# kaimat.net
KiCad netlist of a schematic drawn in EAGLE
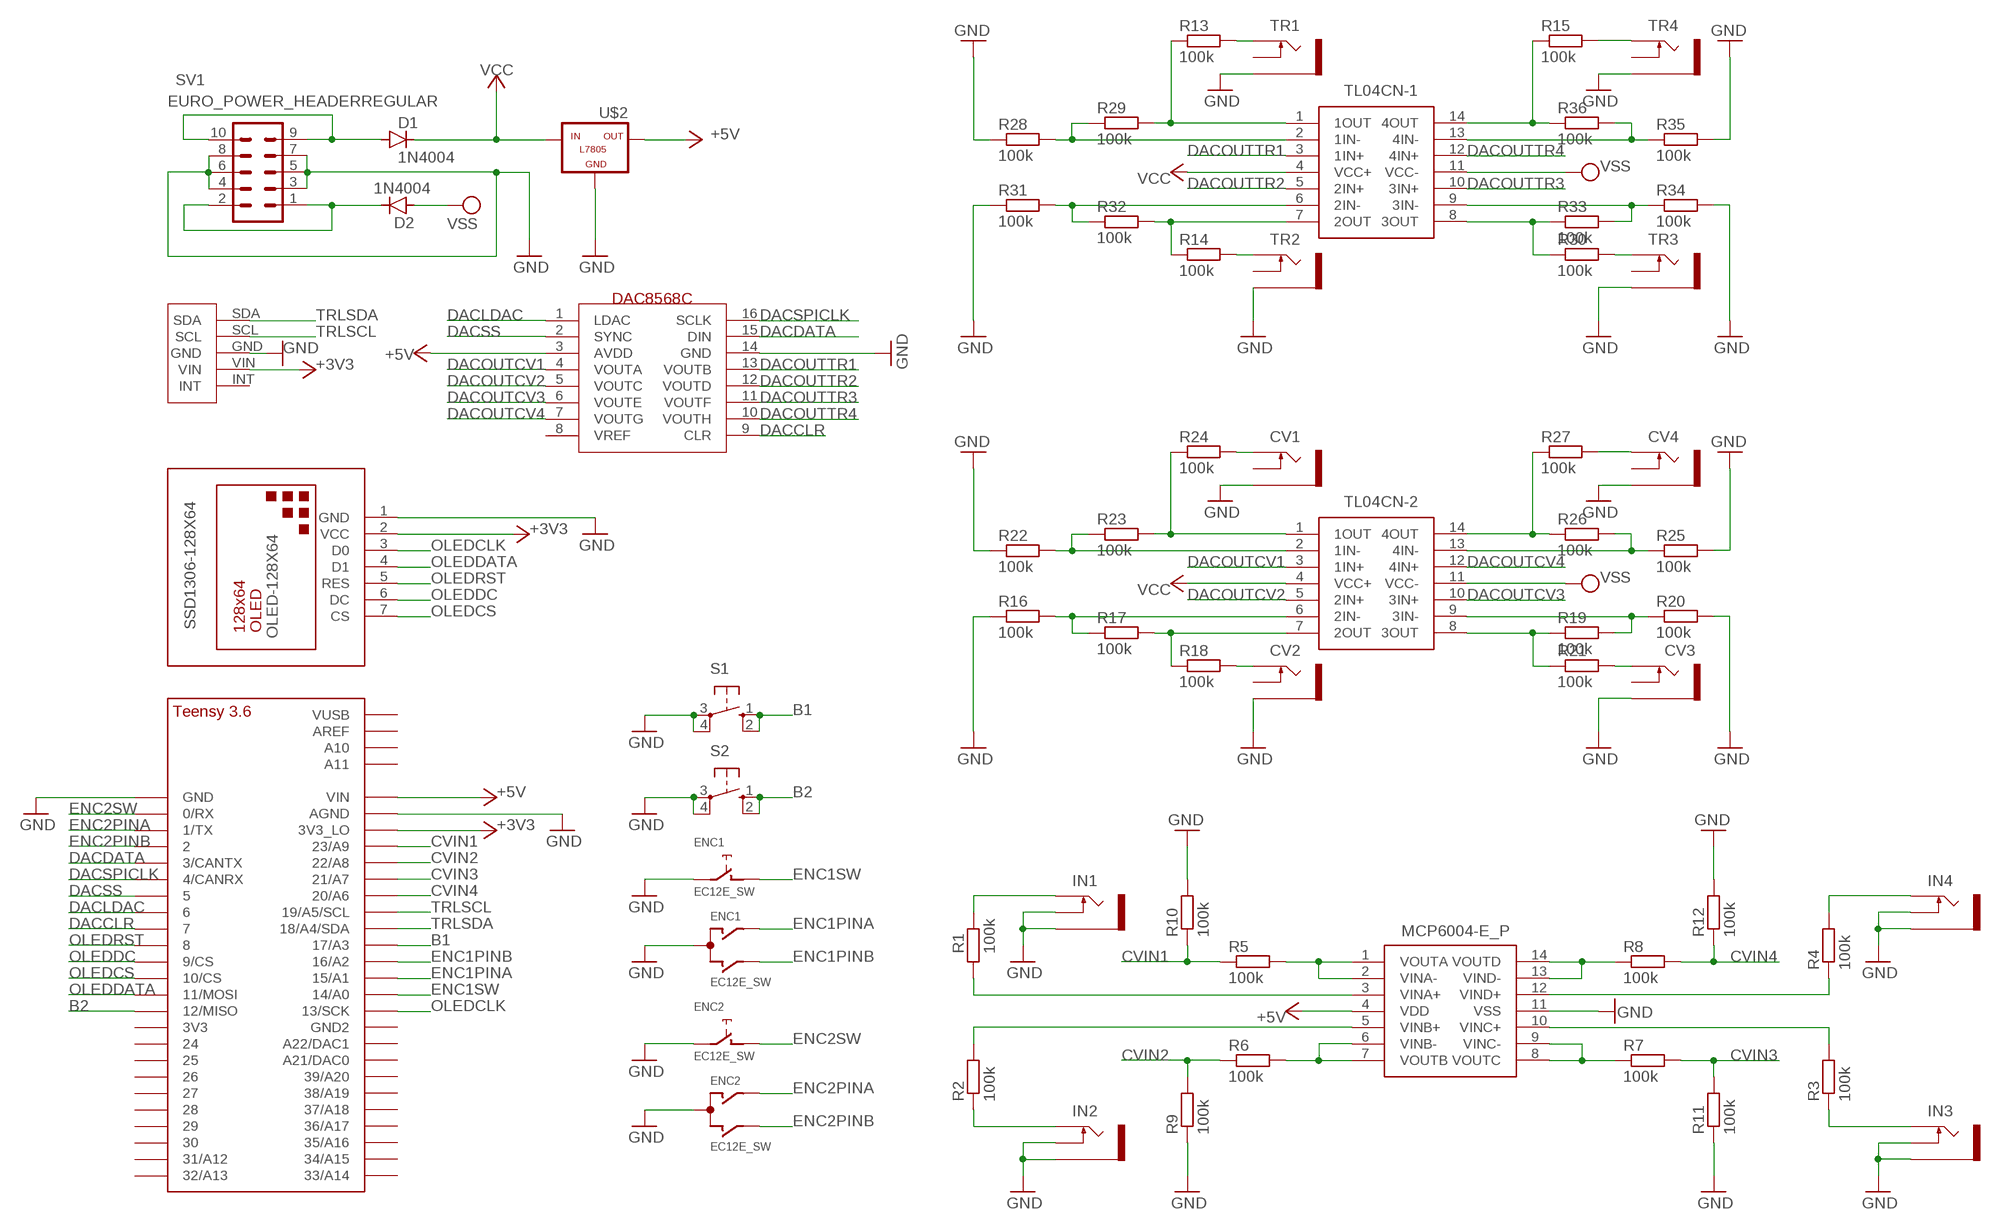
[diagram p0: schematic, sheet 1]

(export (version "E")
  (design (tool "Eeschema 10.0.6"))
  (components
    (comp (ref "CV1")
      (value "THONKICONNNEW")
      (footprint "eagle-import:WQP-PJ301M-12_JACK")
      (libsource (lib "eagle-import") (part "THONKICONNNEW"))
    )
    (comp (ref "CV2")
      (value "THONKICONNNEW")
      (footprint "eagle-import:WQP-PJ301M-12_JACK")
      (libsource (lib "eagle-import") (part "THONKICONNNEW"))
    )
    (comp (ref "CV3")
      (value "THONKICONNNEW")
      (footprint "eagle-import:WQP-PJ301M-12_JACK")
      (libsource (lib "eagle-import") (part "THONKICONNNEW"))
    )
    (comp (ref "CV4")
      (value "THONKICONNNEW")
      (footprint "eagle-import:WQP-PJ301M-12_JACK")
      (libsource (lib "eagle-import") (part "THONKICONNNEW"))
    )
    (comp (ref "D1")
      (value "1N4004")
      (footprint "eagle-import:DO41-10")
      (libsource (lib "eagle-import") (part "1N4004"))
    )
    (comp (ref "D2")
      (value "1N4004")
      (footprint "eagle-import:DO41-10")
      (libsource (lib "eagle-import") (part "1N4004"))
    )
    (comp (ref "DAC8568C")
      (value "DAC8568C")
      (footprint "eagle-import:TSSOP16")
      (libsource (lib "eagle-import") (part "DAC8568C"))
    )
    (comp (ref "ENC1")
      (value "EC12E_SW")
      (footprint "eagle-import:ALPS_EC12E_SW")
      (fields (field (name "MPN") "EC12E2424407"))
      (libsource (lib "eagle-import") (part "EC12E_SW"))
    )
    (comp (ref "ENC2")
      (value "EC12E_SW")
      (footprint "eagle-import:ALPS_EC12E_SW")
      (fields (field (name "MPN") "EC12E2424407"))
      (libsource (lib "eagle-import") (part "EC12E_SW"))
    )
    (comp (ref "IN1")
      (value "THONKICONNNEW")
      (footprint "eagle-import:WQP-PJ301M-12_JACK")
      (libsource (lib "eagle-import") (part "THONKICONNNEW"))
    )
    (comp (ref "IN2")
      (value "THONKICONNNEW")
      (footprint "eagle-import:WQP-PJ301M-12_JACK")
      (libsource (lib "eagle-import") (part "THONKICONNNEW"))
    )
    (comp (ref "IN3")
      (value "THONKICONNNEW")
      (footprint "eagle-import:WQP-PJ301M-12_JACK")
      (libsource (lib "eagle-import") (part "THONKICONNNEW"))
    )
    (comp (ref "IN4")
      (value "THONKICONNNEW")
      (footprint "eagle-import:WQP-PJ301M-12_JACK")
      (libsource (lib "eagle-import") (part "THONKICONNNEW"))
    )
    (comp (ref "MCP6004-E_P")
      (value "MCP6004-E_P")
      (footprint "eagle-import:DIP781W56P254L1918H533Q14N")
      (fields
        (field (name "MANUFACTURER_PART_NUMBER") "mcp6004-e/p")
        (field (name "MOUSER_PART_NUMBER") "579-MCP6004-E/P")
        (field (name "RS_PART_NUMBER") "7386178P")
      )
      (libsource (lib "eagle-import") (part "MCP6004-E_P"))
    )
    (comp (ref "R1")
      (value "100k")
      (footprint "eagle-import:R0805")
      (libsource (lib "eagle-import") (part "R-EU_R0805"))
    )
    (comp (ref "R2")
      (value "100k")
      (footprint "eagle-import:R0805")
      (libsource (lib "eagle-import") (part "R-EU_R0805"))
    )
    (comp (ref "R3")
      (value "100k")
      (footprint "eagle-import:R0805")
      (libsource (lib "eagle-import") (part "R-EU_R0805"))
    )
    (comp (ref "R4")
      (value "100k")
      (footprint "eagle-import:R0805")
      (libsource (lib "eagle-import") (part "R-EU_R0805"))
    )
    (comp (ref "R5")
      (value "100k")
      (footprint "eagle-import:R0805")
      (libsource (lib "eagle-import") (part "R-EU_R0805"))
    )
    (comp (ref "R6")
      (value "100k")
      (footprint "eagle-import:R0805")
      (libsource (lib "eagle-import") (part "R-EU_R0805"))
    )
    (comp (ref "R7")
      (value "100k")
      (footprint "eagle-import:R0805")
      (libsource (lib "eagle-import") (part "R-EU_R0805"))
    )
    (comp (ref "R8")
      (value "100k")
      (footprint "eagle-import:R0805")
      (libsource (lib "eagle-import") (part "R-EU_R0805"))
    )
    (comp (ref "R9")
      (value "100k")
      (footprint "eagle-import:R0805")
      (libsource (lib "eagle-import") (part "R-EU_R0805"))
    )
    (comp (ref "R10")
      (value "100k")
      (footprint "eagle-import:R0805")
      (libsource (lib "eagle-import") (part "R-EU_R0805"))
    )
    (comp (ref "R11")
      (value "100k")
      (footprint "eagle-import:R0805")
      (libsource (lib "eagle-import") (part "R-EU_R0805"))
    )
    (comp (ref "R12")
      (value "100k")
      (footprint "eagle-import:R0805")
      (libsource (lib "eagle-import") (part "R-EU_R0805"))
    )
    (comp (ref "R13")
      (value "100k")
      (footprint "eagle-import:R0805")
      (libsource (lib "eagle-import") (part "R-EU_R0805"))
    )
    (comp (ref "R14")
      (value "100k")
      (footprint "eagle-import:R0805")
      (libsource (lib "eagle-import") (part "R-EU_R0805"))
    )
    (comp (ref "R15")
      (value "100k")
      (footprint "eagle-import:R0805")
      (libsource (lib "eagle-import") (part "R-EU_R0805"))
    )
    (comp (ref "R16")
      (value "100k")
      (footprint "eagle-import:R0805")
      (libsource (lib "eagle-import") (part "R-EU_R0805"))
    )
    (comp (ref "R17")
      (value "100k")
      (footprint "eagle-import:R0805")
      (libsource (lib "eagle-import") (part "R-EU_R0805"))
    )
    (comp (ref "R18")
      (value "100k")
      (footprint "eagle-import:R0805")
      (libsource (lib "eagle-import") (part "R-EU_R0805"))
    )
    (comp (ref "R19")
      (value "100k")
      (footprint "eagle-import:R0805")
      (libsource (lib "eagle-import") (part "R-EU_R0805"))
    )
    (comp (ref "R20")
      (value "100k")
      (footprint "eagle-import:R0805")
      (libsource (lib "eagle-import") (part "R-EU_R0805"))
    )
    (comp (ref "R21")
      (value "100k")
      (footprint "eagle-import:R0805")
      (libsource (lib "eagle-import") (part "R-EU_R0805"))
    )
    (comp (ref "R22")
      (value "100k")
      (footprint "eagle-import:R0805")
      (libsource (lib "eagle-import") (part "R-EU_R0805"))
    )
    (comp (ref "R23")
      (value "100k")
      (footprint "eagle-import:R0805")
      (libsource (lib "eagle-import") (part "R-EU_R0805"))
    )
    (comp (ref "R24")
      (value "100k")
      (footprint "eagle-import:R0805")
      (libsource (lib "eagle-import") (part "R-EU_R0805"))
    )
    (comp (ref "R25")
      (value "100k")
      (footprint "eagle-import:R0805")
      (libsource (lib "eagle-import") (part "R-EU_R0805"))
    )
    (comp (ref "R26")
      (value "100k")
      (footprint "eagle-import:R0805")
      (libsource (lib "eagle-import") (part "R-EU_R0805"))
    )
    (comp (ref "R27")
      (value "100k")
      (footprint "eagle-import:R0805")
      (libsource (lib "eagle-import") (part "R-EU_R0805"))
    )
    (comp (ref "R28")
      (value "100k")
      (footprint "eagle-import:R0805")
      (libsource (lib "eagle-import") (part "R-EU_R0805"))
    )
    (comp (ref "R29")
      (value "100k")
      (footprint "eagle-import:R0805")
      (libsource (lib "eagle-import") (part "R-EU_R0805"))
    )
    (comp (ref "R30")
      (value "100k")
      (footprint "eagle-import:R0805")
      (libsource (lib "eagle-import") (part "R-EU_R0805"))
    )
    (comp (ref "R31")
      (value "100k")
      (footprint "eagle-import:R0805")
      (libsource (lib "eagle-import") (part "R-EU_R0805"))
    )
    (comp (ref "R32")
      (value "100k")
      (footprint "eagle-import:R0805")
      (libsource (lib "eagle-import") (part "R-EU_R0805"))
    )
    (comp (ref "R33")
      (value "100k")
      (footprint "eagle-import:R0805")
      (libsource (lib "eagle-import") (part "R-EU_R0805"))
    )
    (comp (ref "R34")
      (value "100k")
      (footprint "eagle-import:R0805")
      (libsource (lib "eagle-import") (part "R-EU_R0805"))
    )
    (comp (ref "R35")
      (value "100k")
      (footprint "eagle-import:R0805")
      (libsource (lib "eagle-import") (part "R-EU_R0805"))
    )
    (comp (ref "R36")
      (value "100k")
      (footprint "eagle-import:R0805")
      (libsource (lib "eagle-import") (part "R-EU_R0805"))
    )
    (comp (ref "S1")
      (value "10-XX")
      (footprint "eagle-import:B3F-10XX")
      (fields (field (name "MPN") "B3F-1000"))
      (libsource (lib "eagle-import") (part "10-XX"))
    )
    (comp (ref "S2")
      (value "10-XX")
      (footprint "eagle-import:B3F-10XX")
      (fields (field (name "MPN") "B3F-1000"))
      (libsource (lib "eagle-import") (part "10-XX"))
    )
    (comp (ref "SSD1306-128X64")
      (value "OLED-128X64")
      (footprint "eagle-import:DISPLAY-OLED-128X64-SMALL")
      (libsource (lib "eagle-import") (part "OLED-128X64"))
    )
    (comp (ref "SV1")
      (value "EURO_POWER_HEADERREGULAR")
      (footprint "eagle-import:EURO_POWER_HEADER")
      (libsource (lib "eagle-import") (part "EURO_POWER_HEADERREGULAR"))
    )
    (comp (ref "TL04CN-1")
      (value "TL074CN")
      (footprint "eagle-import:DIP794W53P254L1930H508Q14N")
      (fields (field (name "MOUSER_PART_NUMBER") "595-TL074CN") (field (name "RS_PART_NUMBER") "0302621P"))
      (libsource (lib "eagle-import") (part "TL074CN"))
    )
    (comp (ref "TL04CN-2")
      (value "TL074CN")
      (footprint "eagle-import:DIP794W53P254L1930H508Q14N")
      (fields (field (name "MOUSER_PART_NUMBER") "595-TL074CN") (field (name "RS_PART_NUMBER") "0302621P"))
      (libsource (lib "eagle-import") (part "TL074CN"))
    )
    (comp (ref "TR1")
      (value "THONKICONNNEW")
      (footprint "eagle-import:WQP-PJ301M-12_JACK")
      (libsource (lib "eagle-import") (part "THONKICONNNEW"))
    )
    (comp (ref "TR2")
      (value "THONKICONNNEW")
      (footprint "eagle-import:WQP-PJ301M-12_JACK")
      (libsource (lib "eagle-import") (part "THONKICONNNEW"))
    )
    (comp (ref "TR3")
      (value "THONKICONNNEW")
      (footprint "eagle-import:WQP-PJ301M-12_JACK")
      (libsource (lib "eagle-import") (part "THONKICONNNEW"))
    )
    (comp (ref "TR4")
      (value "THONKICONNNEW")
      (footprint "eagle-import:WQP-PJ301M-12_JACK")
      (libsource (lib "eagle-import") (part "THONKICONNNEW"))
    )
    (comp (ref "U$1")
      (value "TEENSY_3.5/3.6_BASIC")
      (footprint "eagle-import:TEENSY_3.5_3.6_BASIC")
      (libsource (lib "eagle-import") (part "TEENSY_3.5/3.6_BASIC"))
    )
    (comp (ref "U$2")
      (value "-L7805")
      (footprint "eagle-import:L7805")
      (libsource (lib "eagle-import") (part "-L7805"))
    )
    (comp (ref "U$4")
      (value "NEOTRELLISKAIMAT2")
      (footprint "eagle-import:NEOTRELLISKAIMAT2")
      (libsource (lib "eagle-import") (part "NEOTRELLISKAIMAT2"))
    )
  )
  (nets
    (net (code "1") (name "+3V3") (class "Default")
      (node (ref "SSD1306-128X64") (pin "2") (pinfunction "VCC_2") (pintype "power_in"))
      (node (ref "U$1") (pin "3V3_LO") (pinfunction "3V3_LO_3V3_LO") (pintype "bidirectional"))
      (node (ref "U$4") (pin "VIN") (pinfunction "VIN_VIN") (pintype "bidirectional"))
    )
    (net (code "2") (name "+5V") (class "Default")
      (node (ref "DAC8568C") (pin "3") (pinfunction "AVDD_3") (pintype "bidirectional"))
      (node (ref "MCP6004-E_P") (pin "4") (pinfunction "VDD_4") (pintype "power_in"))
      (node (ref "U$1") (pin "VIN") (pinfunction "VIN_VIN") (pintype "bidirectional"))
      (node (ref "U$2") (pin "OUT") (pinfunction "OUT_OUT") (pintype "passive"))
    )
    (net (code "3") (name "/B1") (class "Default")
      (node (ref "S1") (pin "1") (pinfunction "S_1") (pintype "passive"))
      (node (ref "S1") (pin "2") (pinfunction "S1_2") (pintype "passive"))
      (node (ref "U$1") (pin "17/A3") (pinfunction "17/A3_17/A3") (pintype "bidirectional"))
    )
    (net (code "4") (name "/B2") (class "Default")
      (node (ref "S2") (pin "1") (pinfunction "S_1") (pintype "passive"))
      (node (ref "S2") (pin "2") (pinfunction "S1_2") (pintype "passive"))
      (node (ref "U$1") (pin "12/MISO") (pinfunction "12/MISO_12/MISO") (pintype "bidirectional"))
    )
    (net (code "5") (name "/CVIN1") (class "Default")
      (node (ref "R10") (pin "1") (pinfunction "1_1") (pintype "passive"))
      (node (ref "R5") (pin "1") (pinfunction "1_1") (pintype "passive"))
      (node (ref "U$1") (pin "23/A9") (pinfunction "23/A9_23/A9") (pintype "bidirectional"))
    )
    (net (code "6") (name "/CVIN2") (class "Default")
      (node (ref "R6") (pin "1") (pinfunction "1_1") (pintype "passive"))
      (node (ref "R9") (pin "2") (pinfunction "2_2") (pintype "passive"))
      (node (ref "U$1") (pin "22/A8") (pinfunction "22/A8_22/A8") (pintype "bidirectional"))
    )
    (net (code "7") (name "/CVIN3") (class "Default")
      (node (ref "R11") (pin "2") (pinfunction "2_2") (pintype "passive"))
      (node (ref "R7") (pin "2") (pinfunction "2_2") (pintype "passive"))
      (node (ref "U$1") (pin "21/A7") (pinfunction "21/A7_21/A7") (pintype "bidirectional"))
    )
    (net (code "8") (name "/CVIN4") (class "Default")
      (node (ref "R12") (pin "1") (pinfunction "1_1") (pintype "passive"))
      (node (ref "R8") (pin "2") (pinfunction "2_2") (pintype "passive"))
      (node (ref "U$1") (pin "20/A6") (pinfunction "20/A6_20/A6") (pintype "bidirectional"))
    )
    (net (code "9") (name "/DACCLR") (class "Default")
      (node (ref "DAC8568C") (pin "9") (pinfunction "CLR_9") (pintype "bidirectional"))
      (node (ref "U$1") (pin "7") (pinfunction "7_7") (pintype "bidirectional"))
    )
    (net (code "10") (name "/DACDATA") (class "Default")
      (node (ref "DAC8568C") (pin "15") (pinfunction "DIN_15") (pintype "bidirectional"))
      (node (ref "U$1") (pin "3/CANTX") (pinfunction "3/CANTX_3/CANTX") (pintype "bidirectional"))
    )
    (net (code "11") (name "/DACLDAC") (class "Default")
      (node (ref "DAC8568C") (pin "1") (pinfunction "LDAC_1") (pintype "bidirectional"))
      (node (ref "U$1") (pin "6") (pinfunction "6_6") (pintype "bidirectional"))
    )
    (net (code "12") (name "/DACOUTCV1") (class "Default")
      (node (ref "DAC8568C") (pin "4") (pinfunction "VOUTA_4") (pintype "bidirectional"))
      (node (ref "TL04CN-2") (pin "3") (pinfunction "1IN+_3") (pintype "input"))
    )
    (net (code "13") (name "/DACOUTCV2") (class "Default")
      (node (ref "DAC8568C") (pin "5") (pinfunction "VOUTC_5") (pintype "bidirectional"))
      (node (ref "TL04CN-2") (pin "5") (pinfunction "2IN+_5") (pintype "input"))
    )
    (net (code "14") (name "/DACOUTCV3") (class "Default")
      (node (ref "DAC8568C") (pin "6") (pinfunction "VOUTE_6") (pintype "bidirectional"))
      (node (ref "TL04CN-2") (pin "10") (pinfunction "3IN+_10") (pintype "input"))
    )
    (net (code "15") (name "/DACOUTCV4") (class "Default")
      (node (ref "DAC8568C") (pin "7") (pinfunction "VOUTG_7") (pintype "bidirectional"))
      (node (ref "TL04CN-2") (pin "12") (pinfunction "4IN+_12") (pintype "input"))
    )
    (net (code "16") (name "/DACOUTTR1") (class "Default")
      (node (ref "DAC8568C") (pin "13") (pinfunction "VOUTB_13") (pintype "bidirectional"))
      (node (ref "TL04CN-1") (pin "3") (pinfunction "1IN+_3") (pintype "input"))
    )
    (net (code "17") (name "/DACOUTTR2") (class "Default")
      (node (ref "DAC8568C") (pin "12") (pinfunction "VOUTD_12") (pintype "bidirectional"))
      (node (ref "TL04CN-1") (pin "5") (pinfunction "2IN+_5") (pintype "input"))
    )
    (net (code "18") (name "/DACOUTTR3") (class "Default")
      (node (ref "DAC8568C") (pin "11") (pinfunction "VOUTF_11") (pintype "bidirectional"))
      (node (ref "TL04CN-1") (pin "10") (pinfunction "3IN+_10") (pintype "input"))
    )
    (net (code "19") (name "/DACOUTTR4") (class "Default")
      (node (ref "DAC8568C") (pin "10") (pinfunction "VOUTH_10") (pintype "bidirectional"))
      (node (ref "TL04CN-1") (pin "12") (pinfunction "4IN+_12") (pintype "input"))
    )
    (net (code "20") (name "/DACSPICLK") (class "Default")
      (node (ref "DAC8568C") (pin "16") (pinfunction "SCLK_16") (pintype "bidirectional"))
      (node (ref "U$1") (pin "4/CANRX") (pinfunction "4/CANRX_4/CANRX") (pintype "bidirectional"))
    )
    (net (code "21") (name "/DACSS") (class "Default")
      (node (ref "DAC8568C") (pin "2") (pinfunction "SYNC_2") (pintype "bidirectional"))
      (node (ref "U$1") (pin "5") (pinfunction "5_5") (pintype "bidirectional"))
    )
    (net (code "22") (name "/ENC1PINA") (class "Default")
      (node (ref "ENC1") (pin "A") (pinfunction "A_A") (pintype "passive"))
      (node (ref "U$1") (pin "15/A1") (pinfunction "15/A1_15/A1") (pintype "bidirectional"))
    )
    (net (code "23") (name "/ENC1PINB") (class "Default")
      (node (ref "ENC1") (pin "B") (pinfunction "B_B") (pintype "passive"))
      (node (ref "U$1") (pin "16/A2") (pinfunction "16/A2_16/A2") (pintype "bidirectional"))
    )
    (net (code "24") (name "/ENC1SW") (class "Default")
      (node (ref "ENC1") (pin "D") (pinfunction "1_D") (pintype "passive"))
      (node (ref "U$1") (pin "14/A0") (pinfunction "14/A0_14/A0") (pintype "bidirectional"))
    )
    (net (code "25") (name "/ENC2PINA") (class "Default")
      (node (ref "ENC2") (pin "A") (pinfunction "A_A") (pintype "passive"))
      (node (ref "U$1") (pin "1/TX") (pinfunction "1/TX_1/TX") (pintype "bidirectional"))
    )
    (net (code "26") (name "/ENC2PINB") (class "Default")
      (node (ref "ENC2") (pin "B") (pinfunction "B_B") (pintype "passive"))
      (node (ref "U$1") (pin "2") (pinfunction "2_2") (pintype "bidirectional"))
    )
    (net (code "27") (name "/ENC2SW") (class "Default")
      (node (ref "ENC2") (pin "D") (pinfunction "1_D") (pintype "passive"))
      (node (ref "U$1") (pin "0/RX") (pinfunction "0/RX_0/RX") (pintype "bidirectional"))
    )
    (net (code "28") (name "/OLEDCLK") (class "Default")
      (node (ref "SSD1306-128X64") (pin "3") (pinfunction "D0_3") (pintype "bidirectional"))
      (node (ref "U$1") (pin "13/SCK") (pinfunction "13/SCK_13/SCK") (pintype "bidirectional"))
    )
    (net (code "29") (name "/OLEDCS") (class "Default")
      (node (ref "SSD1306-128X64") (pin "7") (pinfunction "CS_7") (pintype "bidirectional"))
      (node (ref "U$1") (pin "10/CS") (pinfunction "10/CS_10/CS") (pintype "bidirectional"))
    )
    (net (code "30") (name "/OLEDDATA") (class "Default")
      (node (ref "SSD1306-128X64") (pin "4") (pinfunction "D1_4") (pintype "bidirectional"))
      (node (ref "U$1") (pin "11/MOSI") (pinfunction "11/MOSI_11/MOSI") (pintype "bidirectional"))
    )
    (net (code "31") (name "/OLEDDC") (class "Default")
      (node (ref "SSD1306-128X64") (pin "6") (pinfunction "DC_6") (pintype "bidirectional"))
      (node (ref "U$1") (pin "9/CS") (pinfunction "9/CS_9/CS") (pintype "bidirectional"))
    )
    (net (code "32") (name "/OLEDRST") (class "Default")
      (node (ref "SSD1306-128X64") (pin "5") (pinfunction "RES_5") (pintype "bidirectional"))
      (node (ref "U$1") (pin "8") (pinfunction "8_8") (pintype "bidirectional"))
    )
    (net (code "33") (name "/TRLSCL") (class "Default")
      (node (ref "U$1") (pin "19/A5/SCL") (pinfunction "19/A5/SCL_19/A5/SCL") (pintype "bidirectional"))
      (node (ref "U$4") (pin "SCL") (pinfunction "SCL_SCL") (pintype "bidirectional"))
    )
    (net (code "34") (name "/TRLSDA") (class "Default")
      (node (ref "U$1") (pin "18/A4/SDA") (pinfunction "18/A4/SDA_18/A4/SDA") (pintype "bidirectional"))
      (node (ref "U$4") (pin "SDA") (pinfunction "SDA_SDA") (pintype "bidirectional"))
    )
    (net (code "35") (name "GND") (class "Default")
      (node (ref "CV1") (pin "P$3_SLEEVE") (pinfunction "SLEEVE_P$3_SLEEVE") (pintype "passive"))
      (node (ref "CV2") (pin "P$3_SLEEVE") (pinfunction "SLEEVE_P$3_SLEEVE") (pintype "passive"))
      (node (ref "CV3") (pin "P$3_SLEEVE") (pinfunction "SLEEVE_P$3_SLEEVE") (pintype "passive"))
      (node (ref "CV4") (pin "P$3_SLEEVE") (pinfunction "SLEEVE_P$3_SLEEVE") (pintype "passive"))
      (node (ref "DAC8568C") (pin "14") (pinfunction "GND_14") (pintype "bidirectional"))
      (node (ref "ENC1") (pin "C") (pinfunction "C_C") (pintype "passive"))
      (node (ref "ENC1") (pin "E") (pinfunction "2_E") (pintype "passive"))
      (node (ref "ENC2") (pin "C") (pinfunction "C_C") (pintype "passive"))
      (node (ref "ENC2") (pin "E") (pinfunction "2_E") (pintype "passive"))
      (node (ref "IN1") (pin "P$2_SWITCH") (pinfunction "SWITCH_P$2_SWITCH") (pintype "passive"))
      (node (ref "IN1") (pin "P$3_SLEEVE") (pinfunction "SLEEVE_P$3_SLEEVE") (pintype "passive"))
      (node (ref "IN2") (pin "P$2_SWITCH") (pinfunction "SWITCH_P$2_SWITCH") (pintype "passive"))
      (node (ref "IN2") (pin "P$3_SLEEVE") (pinfunction "SLEEVE_P$3_SLEEVE") (pintype "passive"))
      (node (ref "IN3") (pin "P$2_SWITCH") (pinfunction "SWITCH_P$2_SWITCH") (pintype "passive"))
      (node (ref "IN3") (pin "P$3_SLEEVE") (pinfunction "SLEEVE_P$3_SLEEVE") (pintype "passive"))
      (node (ref "IN4") (pin "P$2_SWITCH") (pinfunction "SWITCH_P$2_SWITCH") (pintype "passive"))
      (node (ref "IN4") (pin "P$3_SLEEVE") (pinfunction "SLEEVE_P$3_SLEEVE") (pintype "passive"))
      (node (ref "MCP6004-E_P") (pin "11") (pinfunction "VSS_11") (pintype "power_in"))
      (node (ref "R10") (pin "2") (pinfunction "2_2") (pintype "passive"))
      (node (ref "R11") (pin "1") (pinfunction "1_1") (pintype "passive"))
      (node (ref "R12") (pin "2") (pinfunction "2_2") (pintype "passive"))
      (node (ref "R16") (pin "1") (pinfunction "1_1") (pintype "passive"))
      (node (ref "R20") (pin "2") (pinfunction "2_2") (pintype "passive"))
      (node (ref "R22") (pin "1") (pinfunction "1_1") (pintype "passive"))
      (node (ref "R25") (pin "2") (pinfunction "2_2") (pintype "passive"))
      (node (ref "R28") (pin "1") (pinfunction "1_1") (pintype "passive"))
      (node (ref "R31") (pin "1") (pinfunction "1_1") (pintype "passive"))
      (node (ref "R34") (pin "2") (pinfunction "2_2") (pintype "passive"))
      (node (ref "R35") (pin "2") (pinfunction "2_2") (pintype "passive"))
      (node (ref "R9") (pin "1") (pinfunction "1_1") (pintype "passive"))
      (node (ref "S1") (pin "3") (pinfunction "P_3") (pintype "passive"))
      (node (ref "S1") (pin "4") (pinfunction "P1_4") (pintype "passive"))
      (node (ref "S2") (pin "3") (pinfunction "P_3") (pintype "passive"))
      (node (ref "S2") (pin "4") (pinfunction "P1_4") (pintype "passive"))
      (node (ref "SSD1306-128X64") (pin "1") (pinfunction "GND_1") (pintype "power_in"))
      (node (ref "SV1") (pin "3") (pinfunction "3_3") (pintype "passive"))
      (node (ref "SV1") (pin "4") (pinfunction "4_4") (pintype "passive"))
      (node (ref "SV1") (pin "5") (pinfunction "5_5") (pintype "passive"))
      (node (ref "SV1") (pin "6") (pinfunction "6_6") (pintype "passive"))
      (node (ref "SV1") (pin "7") (pinfunction "7_7") (pintype "passive"))
      (node (ref "SV1") (pin "8") (pinfunction "8_8") (pintype "passive"))
      (node (ref "TR1") (pin "P$3_SLEEVE") (pinfunction "SLEEVE_P$3_SLEEVE") (pintype "passive"))
      (node (ref "TR2") (pin "P$3_SLEEVE") (pinfunction "SLEEVE_P$3_SLEEVE") (pintype "passive"))
      (node (ref "TR3") (pin "P$3_SLEEVE") (pinfunction "SLEEVE_P$3_SLEEVE") (pintype "passive"))
      (node (ref "TR4") (pin "P$3_SLEEVE") (pinfunction "SLEEVE_P$3_SLEEVE") (pintype "passive"))
      (node (ref "U$1") (pin "AGND") (pinfunction "AGND_AGND") (pintype "bidirectional"))
      (node (ref "U$1") (pin "GND") (pinfunction "GND_GND") (pintype "bidirectional"))
      (node (ref "U$2") (pin "GND") (pinfunction "GND_GND") (pintype "input"))
      (node (ref "U$4") (pin "GND") (pinfunction "GND_GND") (pintype "bidirectional"))
    )
    (net (code "36") (name "Net-(CV1-TIP)") (class "Default")
      (node (ref "CV1") (pin "P$1_TIP") (pinfunction "TIP_P$1_TIP") (pintype "passive"))
      (node (ref "R24") (pin "2") (pinfunction "2_2") (pintype "passive"))
    )
    (net (code "37") (name "Net-(CV2-TIP)") (class "Default")
      (node (ref "CV2") (pin "P$1_TIP") (pinfunction "TIP_P$1_TIP") (pintype "passive"))
      (node (ref "R18") (pin "2") (pinfunction "2_2") (pintype "passive"))
    )
    (net (code "38") (name "Net-(CV3-TIP)") (class "Default")
      (node (ref "CV3") (pin "P$1_TIP") (pinfunction "TIP_P$1_TIP") (pintype "passive"))
      (node (ref "R21") (pin "2") (pinfunction "2_2") (pintype "passive"))
    )
    (net (code "39") (name "Net-(CV4-TIP)") (class "Default")
      (node (ref "CV4") (pin "P$1_TIP") (pinfunction "TIP_P$1_TIP") (pintype "passive"))
      (node (ref "R27") (pin "2") (pinfunction "2_2") (pintype "passive"))
    )
    (net (code "40") (name "Net-(D1-PadA)") (class "Default")
      (node (ref "D1") (pin "A") (pinfunction "A_A") (pintype "passive"))
      (node (ref "SV1") (pin "10") (pinfunction "10_10") (pintype "passive"))
      (node (ref "SV1") (pin "9") (pinfunction "9_9") (pintype "passive"))
    )
    (net (code "41") (name "Net-(D2-PadC)") (class "Default")
      (node (ref "D2") (pin "C") (pinfunction "C_C") (pintype "passive"))
      (node (ref "SV1") (pin "1") (pinfunction "1_1") (pintype "passive"))
      (node (ref "SV1") (pin "2") (pinfunction "2_2") (pintype "passive"))
    )
    (net (code "42") (name "Net-(IN1-TIP)") (class "Default")
      (node (ref "IN1") (pin "P$1_TIP") (pinfunction "TIP_P$1_TIP") (pintype "passive"))
      (node (ref "R1") (pin "2") (pinfunction "2_2") (pintype "passive"))
    )
    (net (code "43") (name "Net-(IN2-TIP)") (class "Default")
      (node (ref "IN2") (pin "P$1_TIP") (pinfunction "TIP_P$1_TIP") (pintype "passive"))
      (node (ref "R2") (pin "1") (pinfunction "1_1") (pintype "passive"))
    )
    (net (code "44") (name "Net-(IN3-TIP)") (class "Default")
      (node (ref "IN3") (pin "P$1_TIP") (pinfunction "TIP_P$1_TIP") (pintype "passive"))
      (node (ref "R3") (pin "1") (pinfunction "1_1") (pintype "passive"))
    )
    (net (code "45") (name "Net-(IN4-TIP)") (class "Default")
      (node (ref "IN4") (pin "P$1_TIP") (pinfunction "TIP_P$1_TIP") (pintype "passive"))
      (node (ref "R4") (pin "2") (pinfunction "2_2") (pintype "passive"))
    )
    (net (code "46") (name "Net-(MCP6004-E_P-VINA+)") (class "Default")
      (node (ref "MCP6004-E_P") (pin "3") (pinfunction "VINA+_3") (pintype "input"))
      (node (ref "R1") (pin "1") (pinfunction "1_1") (pintype "passive"))
    )
    (net (code "47") (name "Net-(MCP6004-E_P-VINA-)") (class "Default")
      (node (ref "MCP6004-E_P") (pin "1") (pinfunction "VOUTA_1") (pintype "output"))
      (node (ref "MCP6004-E_P") (pin "2") (pinfunction "VINA-_2") (pintype "input"))
      (node (ref "R5") (pin "2") (pinfunction "2_2") (pintype "passive"))
    )
    (net (code "48") (name "Net-(MCP6004-E_P-VINB+)") (class "Default")
      (node (ref "MCP6004-E_P") (pin "5") (pinfunction "VINB+_5") (pintype "input"))
      (node (ref "R2") (pin "2") (pinfunction "2_2") (pintype "passive"))
    )
    (net (code "49") (name "Net-(MCP6004-E_P-VINB-)") (class "Default")
      (node (ref "MCP6004-E_P") (pin "6") (pinfunction "VINB-_6") (pintype "input"))
      (node (ref "MCP6004-E_P") (pin "7") (pinfunction "VOUTB_7") (pintype "output"))
      (node (ref "R6") (pin "2") (pinfunction "2_2") (pintype "passive"))
    )
    (net (code "50") (name "Net-(MCP6004-E_P-VINC+)") (class "Default")
      (node (ref "MCP6004-E_P") (pin "10") (pinfunction "VINC+_10") (pintype "input"))
      (node (ref "R3") (pin "2") (pinfunction "2_2") (pintype "passive"))
    )
    (net (code "51") (name "Net-(MCP6004-E_P-VINC-)") (class "Default")
      (node (ref "MCP6004-E_P") (pin "8") (pinfunction "VOUTC_8") (pintype "output"))
      (node (ref "MCP6004-E_P") (pin "9") (pinfunction "VINC-_9") (pintype "input"))
      (node (ref "R7") (pin "1") (pinfunction "1_1") (pintype "passive"))
    )
    (net (code "52") (name "Net-(MCP6004-E_P-VIND+)") (class "Default")
      (node (ref "MCP6004-E_P") (pin "12") (pinfunction "VIND+_12") (pintype "input"))
      (node (ref "R4") (pin "1") (pinfunction "1_1") (pintype "passive"))
    )
    (net (code "53") (name "Net-(MCP6004-E_P-VIND-)") (class "Default")
      (node (ref "MCP6004-E_P") (pin "13") (pinfunction "VIND-_13") (pintype "input"))
      (node (ref "MCP6004-E_P") (pin "14") (pinfunction "VOUTD_14") (pintype "output"))
      (node (ref "R8") (pin "1") (pinfunction "1_1") (pintype "passive"))
    )
    (net (code "54") (name "Net-(TL04CN-1-1IN-)") (class "Default")
      (node (ref "R28") (pin "2") (pinfunction "2_2") (pintype "passive"))
      (node (ref "R29") (pin "1") (pinfunction "1_1") (pintype "passive"))
      (node (ref "TL04CN-1") (pin "2") (pinfunction "1IN-_2") (pintype "input"))
    )
    (net (code "55") (name "Net-(TL04CN-1-1OUT)") (class "Default")
      (node (ref "R13") (pin "1") (pinfunction "1_1") (pintype "passive"))
      (node (ref "R29") (pin "2") (pinfunction "2_2") (pintype "passive"))
      (node (ref "TL04CN-1") (pin "1") (pinfunction "1OUT_1") (pintype "output"))
    )
    (net (code "56") (name "Net-(TL04CN-1-2IN-)") (class "Default")
      (node (ref "R31") (pin "2") (pinfunction "2_2") (pintype "passive"))
      (node (ref "R32") (pin "1") (pinfunction "1_1") (pintype "passive"))
      (node (ref "TL04CN-1") (pin "6") (pinfunction "2IN-_6") (pintype "input"))
    )
    (net (code "57") (name "Net-(TL04CN-1-2OUT)") (class "Default")
      (node (ref "R14") (pin "1") (pinfunction "1_1") (pintype "passive"))
      (node (ref "R32") (pin "2") (pinfunction "2_2") (pintype "passive"))
      (node (ref "TL04CN-1") (pin "7") (pinfunction "2OUT_7") (pintype "output"))
    )
    (net (code "58") (name "Net-(TL04CN-1-3IN-)") (class "Default")
      (node (ref "R33") (pin "2") (pinfunction "2_2") (pintype "passive"))
      (node (ref "R34") (pin "1") (pinfunction "1_1") (pintype "passive"))
      (node (ref "TL04CN-1") (pin "9") (pinfunction "3IN-_9") (pintype "input"))
    )
    (net (code "59") (name "Net-(TL04CN-1-3OUT)") (class "Default")
      (node (ref "R30") (pin "1") (pinfunction "1_1") (pintype "passive"))
      (node (ref "R33") (pin "1") (pinfunction "1_1") (pintype "passive"))
      (node (ref "TL04CN-1") (pin "8") (pinfunction "3OUT_8") (pintype "output"))
    )
    (net (code "60") (name "Net-(TL04CN-1-4IN-)") (class "Default")
      (node (ref "R35") (pin "1") (pinfunction "1_1") (pintype "passive"))
      (node (ref "R36") (pin "2") (pinfunction "2_2") (pintype "passive"))
      (node (ref "TL04CN-1") (pin "13") (pinfunction "4IN-_13") (pintype "input"))
    )
    (net (code "61") (name "Net-(TL04CN-1-4OUT)") (class "Default")
      (node (ref "R15") (pin "1") (pinfunction "1_1") (pintype "passive"))
      (node (ref "R36") (pin "1") (pinfunction "1_1") (pintype "passive"))
      (node (ref "TL04CN-1") (pin "14") (pinfunction "4OUT_14") (pintype "output"))
    )
    (net (code "62") (name "Net-(TL04CN-2-1IN-)") (class "Default")
      (node (ref "R22") (pin "2") (pinfunction "2_2") (pintype "passive"))
      (node (ref "R23") (pin "1") (pinfunction "1_1") (pintype "passive"))
      (node (ref "TL04CN-2") (pin "2") (pinfunction "1IN-_2") (pintype "input"))
    )
    (net (code "63") (name "Net-(TL04CN-2-1OUT)") (class "Default")
      (node (ref "R23") (pin "2") (pinfunction "2_2") (pintype "passive"))
      (node (ref "R24") (pin "1") (pinfunction "1_1") (pintype "passive"))
      (node (ref "TL04CN-2") (pin "1") (pinfunction "1OUT_1") (pintype "output"))
    )
    (net (code "64") (name "Net-(TL04CN-2-2IN-)") (class "Default")
      (node (ref "R16") (pin "2") (pinfunction "2_2") (pintype "passive"))
      (node (ref "R17") (pin "1") (pinfunction "1_1") (pintype "passive"))
      (node (ref "TL04CN-2") (pin "6") (pinfunction "2IN-_6") (pintype "input"))
    )
    (net (code "65") (name "Net-(TL04CN-2-2OUT)") (class "Default")
      (node (ref "R17") (pin "2") (pinfunction "2_2") (pintype "passive"))
      (node (ref "R18") (pin "1") (pinfunction "1_1") (pintype "passive"))
      (node (ref "TL04CN-2") (pin "7") (pinfunction "2OUT_7") (pintype "output"))
    )
    (net (code "66") (name "Net-(TL04CN-2-3IN-)") (class "Default")
      (node (ref "R19") (pin "2") (pinfunction "2_2") (pintype "passive"))
      (node (ref "R20") (pin "1") (pinfunction "1_1") (pintype "passive"))
      (node (ref "TL04CN-2") (pin "9") (pinfunction "3IN-_9") (pintype "input"))
    )
    (net (code "67") (name "Net-(TL04CN-2-3OUT)") (class "Default")
      (node (ref "R19") (pin "1") (pinfunction "1_1") (pintype "passive"))
      (node (ref "R21") (pin "1") (pinfunction "1_1") (pintype "passive"))
      (node (ref "TL04CN-2") (pin "8") (pinfunction "3OUT_8") (pintype "output"))
    )
    (net (code "68") (name "Net-(TL04CN-2-4IN-)") (class "Default")
      (node (ref "R25") (pin "1") (pinfunction "1_1") (pintype "passive"))
      (node (ref "R26") (pin "2") (pinfunction "2_2") (pintype "passive"))
      (node (ref "TL04CN-2") (pin "13") (pinfunction "4IN-_13") (pintype "input"))
    )
    (net (code "69") (name "Net-(TL04CN-2-4OUT)") (class "Default")
      (node (ref "R26") (pin "1") (pinfunction "1_1") (pintype "passive"))
      (node (ref "R27") (pin "1") (pinfunction "1_1") (pintype "passive"))
      (node (ref "TL04CN-2") (pin "14") (pinfunction "4OUT_14") (pintype "output"))
    )
    (net (code "70") (name "Net-(TR1-TIP)") (class "Default")
      (node (ref "R13") (pin "2") (pinfunction "2_2") (pintype "passive"))
      (node (ref "TR1") (pin "P$1_TIP") (pinfunction "TIP_P$1_TIP") (pintype "passive"))
    )
    (net (code "71") (name "Net-(TR2-TIP)") (class "Default")
      (node (ref "R14") (pin "2") (pinfunction "2_2") (pintype "passive"))
      (node (ref "TR2") (pin "P$1_TIP") (pinfunction "TIP_P$1_TIP") (pintype "passive"))
    )
    (net (code "72") (name "Net-(TR3-TIP)") (class "Default")
      (node (ref "R30") (pin "2") (pinfunction "2_2") (pintype "passive"))
      (node (ref "TR3") (pin "P$1_TIP") (pinfunction "TIP_P$1_TIP") (pintype "passive"))
    )
    (net (code "73") (name "Net-(TR4-TIP)") (class "Default")
      (node (ref "R15") (pin "2") (pinfunction "2_2") (pintype "passive"))
      (node (ref "TR4") (pin "P$1_TIP") (pinfunction "TIP_P$1_TIP") (pintype "passive"))
    )
    (net (code "74") (name "VCC") (class "Default")
      (node (ref "D1") (pin "C") (pinfunction "C_C") (pintype "passive"))
      (node (ref "TL04CN-1") (pin "4") (pinfunction "VCC+_4") (pintype "power_in"))
      (node (ref "TL04CN-2") (pin "4") (pinfunction "VCC+_4") (pintype "power_in"))
      (node (ref "U$2") (pin "IN") (pinfunction "IN_IN") (pintype "input"))
    )
    (net (code "75") (name "VSS") (class "Default")
      (node (ref "D2") (pin "A") (pinfunction "A_A") (pintype "passive"))
      (node (ref "TL04CN-1") (pin "11") (pinfunction "VCC-_11") (pintype "power_in"))
      (node (ref "TL04CN-2") (pin "11") (pinfunction "VCC-_11") (pintype "power_in"))
    )
    (net (code "76") (name "unconnected-(CV1-SWITCH-PadP$2_SWITCH)") (class "Default")
      (node (ref "CV1") (pin "P$2_SWITCH") (pinfunction "SWITCH_P$2_SWITCH") (pintype "passive"))
    )
    (net (code "77") (name "unconnected-(CV2-SWITCH-PadP$2_SWITCH)") (class "Default")
      (node (ref "CV2") (pin "P$2_SWITCH") (pinfunction "SWITCH_P$2_SWITCH") (pintype "passive"))
    )
    (net (code "78") (name "unconnected-(CV3-SWITCH-PadP$2_SWITCH)") (class "Default")
      (node (ref "CV3") (pin "P$2_SWITCH") (pinfunction "SWITCH_P$2_SWITCH") (pintype "passive"))
    )
    (net (code "79") (name "unconnected-(CV4-SWITCH-PadP$2_SWITCH)") (class "Default")
      (node (ref "CV4") (pin "P$2_SWITCH") (pinfunction "SWITCH_P$2_SWITCH") (pintype "passive"))
    )
    (net (code "80") (name "unconnected-(DAC8568C-VREF-Pad8)") (class "Default")
      (node (ref "DAC8568C") (pin "8") (pinfunction "VREF_8") (pintype "bidirectional"))
    )
    (net (code "81") (name "unconnected-(TR1-SWITCH-PadP$2_SWITCH)") (class "Default")
      (node (ref "TR1") (pin "P$2_SWITCH") (pinfunction "SWITCH_P$2_SWITCH") (pintype "passive"))
    )
    (net (code "82") (name "unconnected-(TR2-SWITCH-PadP$2_SWITCH)") (class "Default")
      (node (ref "TR2") (pin "P$2_SWITCH") (pinfunction "SWITCH_P$2_SWITCH") (pintype "passive"))
    )
    (net (code "83") (name "unconnected-(TR3-SWITCH-PadP$2_SWITCH)") (class "Default")
      (node (ref "TR3") (pin "P$2_SWITCH") (pinfunction "SWITCH_P$2_SWITCH") (pintype "passive"))
    )
    (net (code "84") (name "unconnected-(TR4-SWITCH-PadP$2_SWITCH)") (class "Default")
      (node (ref "TR4") (pin "P$2_SWITCH") (pinfunction "SWITCH_P$2_SWITCH") (pintype "passive"))
    )
    (net (code "85") (name "unconnected-(U$1-A21{slash}DAC0-Pad21{slash}DAC0)") (class "Default")
      (node (ref "U$1") (pin "21/DAC0") (pinfunction "A21/DAC0_21/DAC0") (pintype "bidirectional"))
    )
    (net (code "86") (name "unconnected-(U$1-Pad3V3)") (class "Default")
      (node (ref "U$1") (pin "3V3") (pinfunction "3V3_3V3") (pintype "bidirectional"))
    )
    (net (code "87") (name "unconnected-(U$1-Pad24)") (class "Default")
      (node (ref "U$1") (pin "24") (pinfunction "24_24") (pintype "bidirectional"))
    )
    (net (code "88") (name "unconnected-(U$1-Pad25)") (class "Default")
      (node (ref "U$1") (pin "25") (pinfunction "25_25") (pintype "bidirectional"))
    )
    (net (code "89") (name "unconnected-(U$1-Pad26)") (class "Default")
      (node (ref "U$1") (pin "26") (pinfunction "26_26") (pintype "bidirectional"))
    )
    (net (code "90") (name "unconnected-(U$1-Pad27)") (class "Default")
      (node (ref "U$1") (pin "27") (pinfunction "27_27") (pintype "bidirectional"))
    )
    (net (code "91") (name "unconnected-(U$1-Pad28)") (class "Default")
      (node (ref "U$1") (pin "28") (pinfunction "28_28") (pintype "bidirectional"))
    )
    (net (code "92") (name "unconnected-(U$1-Pad29)") (class "Default")
      (node (ref "U$1") (pin "29") (pinfunction "29_29") (pintype "bidirectional"))
    )
    (net (code "93") (name "unconnected-(U$1-Pad30)") (class "Default")
      (node (ref "U$1") (pin "30") (pinfunction "30_30") (pintype "bidirectional"))
    )
    (net (code "94") (name "unconnected-(U$1-Pad31{slash}A12)") (class "Default")
      (node (ref "U$1") (pin "31/A12") (pinfunction "31/A12_31/A12") (pintype "bidirectional"))
    )
    (net (code "95") (name "unconnected-(U$1-Pad32{slash}A13)") (class "Default")
      (node (ref "U$1") (pin "32/A13") (pinfunction "32/A13_32/A13") (pintype "bidirectional"))
    )
    (net (code "96") (name "unconnected-(U$1-Pad33{slash}A14)") (class "Default")
      (node (ref "U$1") (pin "33/A14") (pinfunction "33/A14_33/A14") (pintype "bidirectional"))
    )
    (net (code "97") (name "unconnected-(U$1-Pad34{slash}A15)") (class "Default")
      (node (ref "U$1") (pin "34/A15") (pinfunction "34/A15_34/A15") (pintype "bidirectional"))
    )
    (net (code "98") (name "unconnected-(U$1-Pad35{slash}A16)") (class "Default")
      (node (ref "U$1") (pin "35/A16") (pinfunction "35/A16_35/A16") (pintype "bidirectional"))
    )
    (net (code "99") (name "unconnected-(U$1-Pad36{slash}A17)") (class "Default")
      (node (ref "U$1") (pin "36/A17") (pinfunction "36/A17_36/A17") (pintype "bidirectional"))
    )
    (net (code "100") (name "unconnected-(U$1-Pad37{slash}A18)") (class "Default")
      (node (ref "U$1") (pin "37/A18") (pinfunction "37/A18_37/A18") (pintype "bidirectional"))
    )
    (net (code "101") (name "unconnected-(U$1-Pad38{slash}A19)") (class "Default")
      (node (ref "U$1") (pin "38/A19") (pinfunction "38/A19_38/A19") (pintype "bidirectional"))
    )
    (net (code "102") (name "unconnected-(U$1-Pad39{slash}A20)") (class "Default")
      (node (ref "U$1") (pin "39/A20") (pinfunction "39/A20_39/A20") (pintype "bidirectional"))
    )
    (net (code "103") (name "unconnected-(U$1-PadA10)") (class "Default")
      (node (ref "U$1") (pin "A10") (pinfunction "A10_A10") (pintype "bidirectional"))
    )
    (net (code "104") (name "unconnected-(U$1-PadA11)") (class "Default")
      (node (ref "U$1") (pin "A11") (pinfunction "A11_A11") (pintype "bidirectional"))
    )
    (net (code "105") (name "unconnected-(U$1-PadA22{slash}DAC1)") (class "Default")
      (node (ref "U$1") (pin "A22/DAC1") (pinfunction "A22/DAC1_A22/DAC1") (pintype "bidirectional"))
    )
    (net (code "106") (name "unconnected-(U$1-PadAREF)") (class "Default")
      (node (ref "U$1") (pin "AREF") (pinfunction "AREF_AREF") (pintype "bidirectional"))
    )
    (net (code "107") (name "unconnected-(U$1-PadGND2)") (class "Default")
      (node (ref "U$1") (pin "GND2") (pinfunction "GND2_GND2") (pintype "bidirectional"))
    )
    (net (code "108") (name "unconnected-(U$1-PadVUSB)") (class "Default")
      (node (ref "U$1") (pin "VUSB") (pinfunction "VUSB_VUSB") (pintype "bidirectional"))
    )
    (net (code "109") (name "unconnected-(U$4-PadINT)") (class "Default")
      (node (ref "U$4") (pin "INT") (pinfunction "INT_INT") (pintype "bidirectional"))
    )
  )
)
